# STM32.net
KiCad netlist of a schematic drawn in Altium Designer
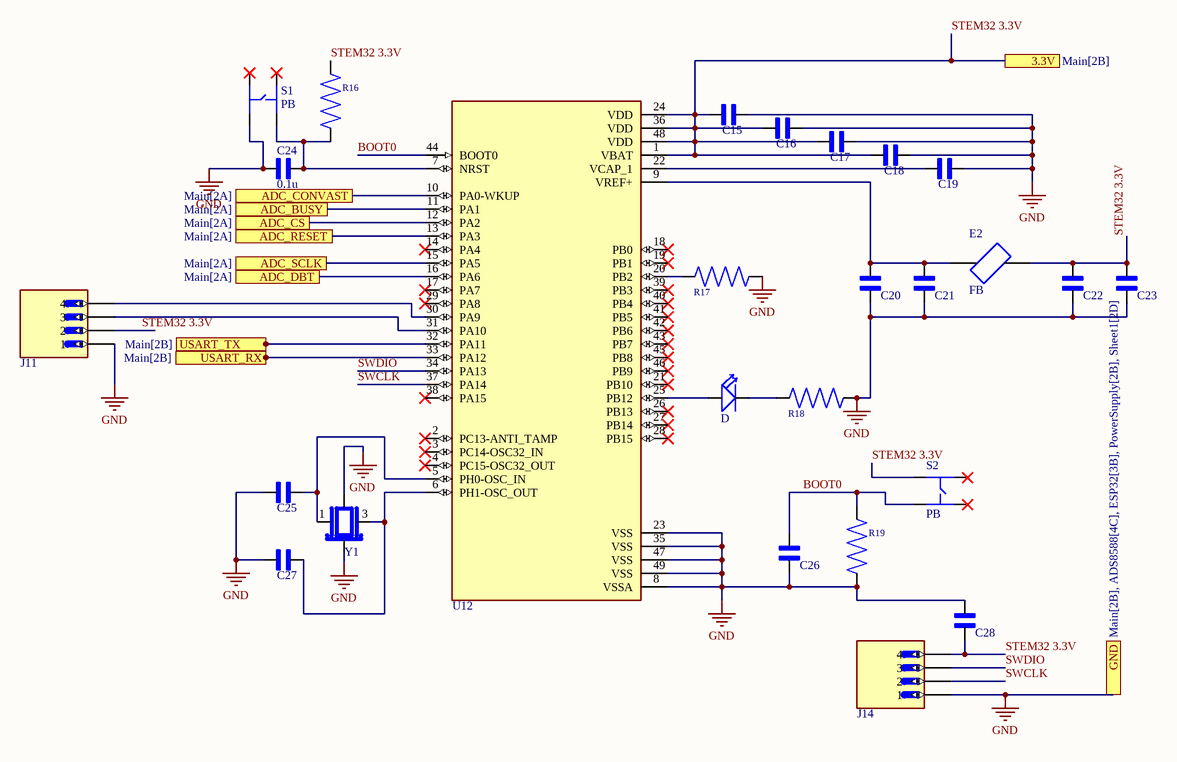
[diagram p0: STM32.SchDoc]

(export (version "E")
  (design (tool "Eeschema 10.0.6"))
  (components
    (comp (ref "C15")
      (value "CAP603")
      (footprint "CAP603")
      (description "0.1 ÂµF Â±5% 10V Ceramic Capacitor X7R 0603 (1608 Metric)")
      (fields (field (name "MF") "Vishay") (field (name "MP") "VJ0603Y104JXQCW1BC"))
      (libsource (lib "ESP32-S3-WROOM-1-N16R8") (part "CAP603"))
    )
    (comp (ref "C16")
      (value "CAP603")
      (footprint "CAP603")
      (description "0.1 ÂµF Â±5% 10V Ceramic Capacitor X7R 0603 (1608 Metric)")
      (fields (field (name "MF") "Vishay") (field (name "MP") "VJ0603Y104JXQCW1BC"))
      (libsource (lib "ESP32-S3-WROOM-1-N16R8") (part "CAP603"))
    )
    (comp (ref "C17")
      (value "CAP603")
      (footprint "CAP603")
      (description "0.1 ÂµF Â±5% 10V Ceramic Capacitor X7R 0603 (1608 Metric)")
      (fields (field (name "MF") "Vishay") (field (name "MP") "VJ0603Y104JXQCW1BC"))
      (libsource (lib "ESP32-S3-WROOM-1-N16R8") (part "CAP603"))
    )
    (comp (ref "C18")
      (value "CAP603")
      (footprint "CAP603")
      (description "0.1 ÂµF Â±5% 10V Ceramic Capacitor X7R 0603 (1608 Metric)")
      (fields (field (name "MF") "Vishay") (field (name "MP") "VJ0603Y104JXQCW1BC"))
      (libsource (lib "ESP32-S3-WROOM-1-N16R8") (part "CAP603"))
    )
    (comp (ref "C19")
      (value "CAP603")
      (footprint "CAP603")
      (description "0.1 ÂµF Â±5% 10V Ceramic Capacitor X7R 0603 (1608 Metric)")
      (fields (field (name "MF") "Vishay") (field (name "MP") "VJ0603Y104JXQCW1BC"))
      (libsource (lib "ESP32-S3-WROOM-1-N16R8") (part "CAP603"))
    )
    (comp (ref "C20")
      (value "CAP603")
      (footprint "CAP603")
      (description "0.1 ÂµF Â±5% 10V Ceramic Capacitor X7R 0603 (1608 Metric)")
      (fields (field (name "MF") "Vishay") (field (name "MP") "VJ0603Y104JXQCW1BC"))
      (libsource (lib "") (part "CAP603_1"))
    )
    (comp (ref "C21")
      (value "CAP603")
      (footprint "CAP603")
      (description "0.1 ÂµF Â±5% 10V Ceramic Capacitor X7R 0603 (1608 Metric)")
      (fields (field (name "MF") "Vishay") (field (name "MP") "VJ0603Y104JXQCW1BC"))
      (libsource (lib "") (part "CAP603_1"))
    )
    (comp (ref "C22")
      (value "CAP603")
      (footprint "CAP603")
      (description "0.1 ÂµF Â±5% 10V Ceramic Capacitor X7R 0603 (1608 Metric)")
      (fields (field (name "MF") "Vishay") (field (name "MP") "VJ0603Y104JXQCW1BC"))
      (libsource (lib "") (part "CAP603_1"))
    )
    (comp (ref "C23")
      (value "CAP603")
      (footprint "CAP603")
      (description "0.1 ÂµF Â±5% 10V Ceramic Capacitor X7R 0603 (1608 Metric)")
      (fields (field (name "MF") "Vishay") (field (name "MP") "VJ0603Y104JXQCW1BC"))
      (libsource (lib "") (part "CAP603_1"))
    )
    (comp (ref "C24")
      (value "0.1u")
      (footprint "0603Capacitor")
      (description "100nf,X7R,50V")
      (fields (field (name "MF") "AVX") (field (name "MP") "0603YC223KAT2A"))
      (libsource (lib "Schlib1") (part "0603_0.1u"))
    )
    (comp (ref "C25")
      (value "CAP603")
      (footprint "CAP603")
      (description "0.1 ÂµF Â±5% 10V Ceramic Capacitor X7R 0603 (1608 Metric)")
      (fields (field (name "MF") "Vishay") (field (name "MP") "VJ0603Y104JXQCW1BC"))
      (libsource (lib "ESP32-S3-WROOM-1-N16R8") (part "CAP603"))
    )
    (comp (ref "C26")
      (value "CAP603")
      (footprint "CAP603")
      (description "0.1 ÂµF Â±5% 10V Ceramic Capacitor X7R 0603 (1608 Metric)")
      (fields (field (name "MF") "Vishay") (field (name "MP") "VJ0603Y104JXQCW1BC"))
      (libsource (lib "") (part "CAP603_1"))
    )
    (comp (ref "C27")
      (value "CAP603")
      (footprint "CAP603")
      (description "0.1 ÂµF Â±5% 10V Ceramic Capacitor X7R 0603 (1608 Metric)")
      (fields (field (name "MF") "Vishay") (field (name "MP") "VJ0603Y104JXQCW1BC"))
      (libsource (lib "ESP32-S3-WROOM-1-N16R8") (part "CAP603"))
    )
    (comp (ref "C28")
      (value "CAP603")
      (footprint "CAP603")
      (description "0.1 ÂµF Â±5% 10V Ceramic Capacitor X7R 0603 (1608 Metric)")
      (fields (field (name "MF") "Vishay") (field (name "MP") "VJ0603Y104JXQCW1BC"))
      (libsource (lib "") (part "CAP603_1"))
    )
    (comp (ref "D")
      (value "SMD-LED-YELLOW-WHITE(0603)")
      (footprint "LED-0603")
      (description "SMD LED Yellow-White")
      (fields (field (name "MF") "Chengguangxing") (field (name "MP") "ADL-0603W"))
      (libsource (lib "ESP32-S3-WROOM-1-N16R8") (part "SMD-LED-YELLOW-WHITE(0603)"))
    )
    (comp (ref "E2")
      (value "FB")
      (footprint "FB_MI1206K601R-10")
      (description "600 Ohms @ 100 MHz 1 Power, Signal Line Ferrite Bead 1206 (3216 Metric) 1.5A 80mOhm")
      (fields (field (name "MF") "Laird-Signal Integrity") (field (name "MP") "MI1206K601R-10"))
      (libsource (lib "Schlib1") (part "MI1206K601R-10"))
    )
    (comp (ref "J11")
      (value "4-pin header")
      (footprint "4-pin header")
      (fields (field (name "MF") "FCI") (field (name "MP") "68000-104HLF"))
      (libsource (lib "ESP32-S3-WROOM-1-N16R8") (part "4-pin header"))
    )
    (comp (ref "J14")
      (value "4-pin header")
      (footprint "4-pin header")
      (fields (field (name "MF") "FCI") (field (name "MP") "68000-104HLF"))
      (libsource (lib "ESP32-S3-WROOM-1-N16R8") (part "4-pin header"))
    )
    (comp (ref "R16")
      (value "RES-603")
      (footprint "CAP603")
      (fields (field (name "MF") "Yageo") (field (name "MP") "RC0805FR-0710KL"))
      (libsource (lib "ESP32-S3-WROOM-1-N16R8") (part "RES-603"))
    )
    (comp (ref "R17")
      (value "RES-603")
      (footprint "CAP603")
      (fields (field (name "MF") "Yageo") (field (name "MP") "RC0805FR-0710KL"))
      (libsource (lib "ESP32-S3-WROOM-1-N16R8") (part "RES-603"))
    )
    (comp (ref "R18")
      (value "RES-603")
      (footprint "CAP603")
      (fields (field (name "MF") "Yageo") (field (name "MP") "RC0805FR-0710KL"))
      (libsource (lib "ESP32-S3-WROOM-1-N16R8") (part "RES-603"))
    )
    (comp (ref "R19")
      (value "RES-603")
      (footprint "CAP603")
      (fields (field (name "MF") "Yageo") (field (name "MP") "RC0805FR-0710KL"))
      (libsource (lib "ESP32-S3-WROOM-1-N16R8") (part "RES-603"))
    )
    (comp (ref "S1") (value "PB") (footprint "Push_button") (libsource (lib "Schlib1") (part "PushButton")))
    (comp (ref "S2") (value "PB") (footprint "Push_button") (libsource (lib "Schlib1") (part "PushButton")))
    (comp (ref "U12")
      (value "STM32F411CEU6TR")
      (footprint "STM32F411CEU6TR")
      (fields (field (name "MF") "STMicroelectronics"))
      (libsource (lib "ESP32-S3-WROOM-1-N16R8") (part "STM32F411CEU6TR"))
    )
    (comp (ref "Y1")
      (value "25 MHz oscillator")
      (footprint "25 MHz oscillator")
      (description "25 MHz 10ppm Crystal 18pF 30 Ohms 4-SMD, No Lead (3.20mm x 2.50mm)")
      (fields (field (name "MF") "Raltron Electronics") (field (name "MP") "RH100-25.000-18-F-1015-TR-NS2"))
      (libsource (lib "ESP32-S3-WROOM-1-N16R8") (part "25 MHz oscillator"))
    )
  )
  (nets
    (net (code "1") (name "/ADC_BUSY") (class "Default")
      (node (ref "U12") (pin "11") (pinfunction "PA1_11") (pintype "bidirectional"))
    )
    (net (code "2") (name "/ADC_CONVAST") (class "Default")
      (node (ref "U12") (pin "10") (pinfunction "PA0-WKUP_10") (pintype "bidirectional"))
    )
    (net (code "3") (name "/ADC_CS") (class "Default")
      (node (ref "U12") (pin "12") (pinfunction "PA2_12") (pintype "bidirectional"))
    )
    (net (code "4") (name "/ADC_DBT") (class "Default")
      (node (ref "U12") (pin "16") (pinfunction "PA6_16") (pintype "bidirectional"))
    )
    (net (code "5") (name "/ADC_RESET") (class "Default")
      (node (ref "U12") (pin "13") (pinfunction "PA3_13") (pintype "bidirectional"))
    )
    (net (code "6") (name "/ADC_SCLK") (class "Default")
      (node (ref "U12") (pin "15") (pinfunction "PA5_15") (pintype "bidirectional"))
    )
    (net (code "7") (name "/BOOT0") (class "Default")
      (node (ref "C26") (pin "2") (pinfunction "2_2") (pintype "passive"))
      (node (ref "R19") (pin "2") (pinfunction "2_2") (pintype "passive"))
      (node (ref "S2") (pin "3") (pinfunction "3_3") (pintype "passive"))
      (node (ref "U12") (pin "44") (pinfunction "BOOT0_44") (pintype "input"))
    )
    (net (code "8") (name "/STEM32 3.3V") (class "Default")
      (node (ref "C15") (pin "1") (pinfunction "1_1") (pintype "passive"))
      (node (ref "C16") (pin "1") (pinfunction "1_1") (pintype "passive"))
      (node (ref "C17") (pin "1") (pinfunction "1_1") (pintype "passive"))
      (node (ref "C18") (pin "1") (pinfunction "1_1") (pintype "passive"))
      (node (ref "C22") (pin "2") (pinfunction "2_2") (pintype "passive"))
      (node (ref "C23") (pin "2") (pinfunction "2_2") (pintype "passive"))
      (node (ref "C28") (pin "1") (pinfunction "1_1") (pintype "passive"))
      (node (ref "E2") (pin "2") (pinfunction "2_2") (pintype "passive"))
      (node (ref "J11") (pin "2") (pinfunction "2_2") (pintype "bidirectional"))
      (node (ref "J14") (pin "4") (pinfunction "4_4") (pintype "bidirectional"))
      (node (ref "R16") (pin "2") (pinfunction "2_2") (pintype "passive"))
      (node (ref "S2") (pin "1") (pinfunction "1_1") (pintype "passive"))
      (node (ref "U12") (pin "1") (pinfunction "VBAT_1") (pintype "passive"))
      (node (ref "U12") (pin "24") (pinfunction "VDD_24") (pintype "passive"))
      (node (ref "U12") (pin "36") (pinfunction "VDD_36") (pintype "passive"))
      (node (ref "U12") (pin "48") (pinfunction "VDD_48") (pintype "passive"))
    )
    (net (code "9") (name "/SWCLK") (class "Default")
      (node (ref "J14") (pin "2") (pinfunction "2_2") (pintype "bidirectional"))
      (node (ref "U12") (pin "37") (pinfunction "PA14_37") (pintype "bidirectional"))
    )
    (net (code "10") (name "/SWDIO") (class "Default")
      (node (ref "J14") (pin "3") (pinfunction "3_3") (pintype "bidirectional"))
      (node (ref "U12") (pin "34") (pinfunction "PA13_34") (pintype "bidirectional"))
    )
    (net (code "11") (name "/USART_RX") (class "Default")
      (node (ref "U12") (pin "33") (pinfunction "PA12_33") (pintype "bidirectional"))
    )
    (net (code "12") (name "/USART_TX") (class "Default")
      (node (ref "U12") (pin "32") (pinfunction "PA11_32") (pintype "bidirectional"))
    )
    (net (code "13") (name "GND") (class "Default")
      (node (ref "C15") (pin "2") (pinfunction "2_2") (pintype "passive"))
      (node (ref "C16") (pin "2") (pinfunction "2_2") (pintype "passive"))
      (node (ref "C17") (pin "2") (pinfunction "2_2") (pintype "passive"))
      (node (ref "C18") (pin "2") (pinfunction "2_2") (pintype "passive"))
      (node (ref "C19") (pin "2") (pinfunction "2_2") (pintype "passive"))
      (node (ref "C20") (pin "1") (pinfunction "1_1") (pintype "passive"))
      (node (ref "C21") (pin "1") (pinfunction "1_1") (pintype "passive"))
      (node (ref "C22") (pin "1") (pinfunction "1_1") (pintype "passive"))
      (node (ref "C23") (pin "1") (pinfunction "1_1") (pintype "passive"))
      (node (ref "C24") (pin "1") (pinfunction "1_1") (pintype "passive"))
      (node (ref "C25") (pin "1") (pinfunction "1_1") (pintype "passive"))
      (node (ref "C26") (pin "1") (pinfunction "1_1") (pintype "passive"))
      (node (ref "C27") (pin "1") (pinfunction "1_1") (pintype "passive"))
      (node (ref "C28") (pin "2") (pinfunction "2_2") (pintype "passive"))
      (node (ref "J11") (pin "1") (pinfunction "1_1") (pintype "bidirectional"))
      (node (ref "J14") (pin "1") (pinfunction "1_1") (pintype "bidirectional"))
      (node (ref "R17") (pin "2") (pinfunction "2_2") (pintype "passive"))
      (node (ref "R18") (pin "2") (pinfunction "2_2") (pintype "passive"))
      (node (ref "R19") (pin "1") (pinfunction "1_1") (pintype "passive"))
      (node (ref "S1") (pin "1") (pinfunction "1_1") (pintype "passive"))
      (node (ref "U12") (pin "23") (pinfunction "VSS_23") (pintype "passive"))
      (node (ref "U12") (pin "35") (pinfunction "VSS_35") (pintype "passive"))
      (node (ref "U12") (pin "47") (pinfunction "VSS_47") (pintype "passive"))
      (node (ref "U12") (pin "49") (pinfunction "VSS_49") (pintype "passive"))
      (node (ref "U12") (pin "8") (pinfunction "VSSA_8") (pintype "passive"))
      (node (ref "Y1") (pin "2") (pinfunction "GND_2") (pintype "power_in"))
      (node (ref "Y1") (pin "4") (pinfunction "GND_4") (pintype "power_in"))
    )
    (net (code "14") (name "Net-(D-PadNEG)") (class "Default")
      (node (ref "D") (pin "NEG") (pinfunction "NEG_NEG") (pintype "passive"))
      (node (ref "R18") (pin "1") (pinfunction "1_1") (pintype "passive"))
    )
    (net (code "15") (name "Net-(U12-NRST)") (class "Default")
      (node (ref "C24") (pin "2") (pinfunction "2_2") (pintype "passive"))
      (node (ref "R16") (pin "1") (pinfunction "1_1") (pintype "passive"))
      (node (ref "S1") (pin "3") (pinfunction "3_3") (pintype "passive"))
      (node (ref "U12") (pin "7") (pinfunction "NRST_7") (pintype "bidirectional"))
    )
    (net (code "16") (name "Net-(U12-PA9)") (class "Default")
      (node (ref "J11") (pin "4") (pinfunction "4_4") (pintype "bidirectional"))
      (node (ref "U12") (pin "30") (pinfunction "PA9_30") (pintype "bidirectional"))
    )
    (net (code "17") (name "Net-(U12-PA10)") (class "Default")
      (node (ref "J11") (pin "3") (pinfunction "3_3") (pintype "bidirectional"))
      (node (ref "U12") (pin "31") (pinfunction "PA10_31") (pintype "bidirectional"))
    )
    (net (code "18") (name "Net-(U12-PB2)") (class "Default")
      (node (ref "R17") (pin "1") (pinfunction "1_1") (pintype "passive"))
      (node (ref "U12") (pin "20") (pinfunction "PB2_20") (pintype "bidirectional"))
    )
    (net (code "19") (name "Net-(U12-PB12)") (class "Default")
      (node (ref "D") (pin "POS") (pinfunction "POS_POS") (pintype "passive"))
      (node (ref "U12") (pin "25") (pinfunction "PB12_25") (pintype "bidirectional"))
    )
    (net (code "20") (name "Net-(U12-PH0-OSC_IN)") (class "Default")
      (node (ref "C25") (pin "2") (pinfunction "2_2") (pintype "passive"))
      (node (ref "U12") (pin "5") (pinfunction "PH0-OSC_IN_5") (pintype "bidirectional"))
      (node (ref "Y1") (pin "1") (pinfunction "1_1") (pintype "passive"))
    )
    (net (code "21") (name "Net-(U12-PH1-OSC_OUT)") (class "Default")
      (node (ref "C27") (pin "2") (pinfunction "2_2") (pintype "passive"))
      (node (ref "U12") (pin "6") (pinfunction "PH1-OSC_OUT_6") (pintype "bidirectional"))
      (node (ref "Y1") (pin "3") (pinfunction "3_3") (pintype "passive"))
    )
    (net (code "22") (name "Net-(U12-VCAP_1)") (class "Default")
      (node (ref "C19") (pin "1") (pinfunction "1_1") (pintype "passive"))
      (node (ref "U12") (pin "22") (pinfunction "VCAP_1_22") (pintype "power_in"))
    )
    (net (code "23") (name "Net-(U12-VREF+)") (class "Default")
      (node (ref "C20") (pin "2") (pinfunction "2_2") (pintype "passive"))
      (node (ref "C21") (pin "2") (pinfunction "2_2") (pintype "passive"))
      (node (ref "E2") (pin "1") (pinfunction "1_1") (pintype "passive"))
      (node (ref "U12") (pin "9") (pinfunction "VREF+_9") (pintype "power_in"))
    )
    (net (code "24") (name "unconnected-(S1-Pad2)") (class "Default")
      (node (ref "S1") (pin "2") (pinfunction "2_2") (pintype "passive+no_connect"))
    )
    (net (code "25") (name "unconnected-(S1-Pad4)") (class "Default")
      (node (ref "S1") (pin "4") (pinfunction "4_4") (pintype "passive"))
    )
    (net (code "26") (name "unconnected-(S2-Pad2)") (class "Default")
      (node (ref "S2") (pin "2") (pinfunction "2_2") (pintype "passive+no_connect"))
    )
    (net (code "27") (name "unconnected-(S2-Pad4)") (class "Default")
      (node (ref "S2") (pin "4") (pinfunction "4_4") (pintype "passive"))
    )
    (net (code "28") (name "unconnected-(U12-PA4-Pad14)") (class "Default")
      (node (ref "U12") (pin "14") (pinfunction "PA4_14") (pintype "bidirectional+no_connect"))
    )
    (net (code "29") (name "unconnected-(U12-PA7-Pad17)") (class "Default")
      (node (ref "U12") (pin "17") (pinfunction "PA7_17") (pintype "bidirectional+no_connect"))
    )
    (net (code "30") (name "unconnected-(U12-PA8-Pad29)") (class "Default")
      (node (ref "U12") (pin "29") (pinfunction "PA8_29") (pintype "bidirectional+no_connect"))
    )
    (net (code "31") (name "unconnected-(U12-PA15-Pad38)") (class "Default")
      (node (ref "U12") (pin "38") (pinfunction "PA15_38") (pintype "bidirectional+no_connect"))
    )
    (net (code "32") (name "unconnected-(U12-PB0-Pad18)") (class "Default")
      (node (ref "U12") (pin "18") (pinfunction "PB0_18") (pintype "bidirectional+no_connect"))
    )
    (net (code "33") (name "unconnected-(U12-PB1-Pad19)") (class "Default")
      (node (ref "U12") (pin "19") (pinfunction "PB1_19") (pintype "bidirectional+no_connect"))
    )
    (net (code "34") (name "unconnected-(U12-PB3-Pad39)") (class "Default")
      (node (ref "U12") (pin "39") (pinfunction "PB3_39") (pintype "bidirectional+no_connect"))
    )
    (net (code "35") (name "unconnected-(U12-PB4-Pad40)") (class "Default")
      (node (ref "U12") (pin "40") (pinfunction "PB4_40") (pintype "bidirectional+no_connect"))
    )
    (net (code "36") (name "unconnected-(U12-PB5-Pad41)") (class "Default")
      (node (ref "U12") (pin "41") (pinfunction "PB5_41") (pintype "bidirectional+no_connect"))
    )
    (net (code "37") (name "unconnected-(U12-PB6-Pad42)") (class "Default")
      (node (ref "U12") (pin "42") (pinfunction "PB6_42") (pintype "bidirectional+no_connect"))
    )
    (net (code "38") (name "unconnected-(U12-PB7-Pad43)") (class "Default")
      (node (ref "U12") (pin "43") (pinfunction "PB7_43") (pintype "bidirectional+no_connect"))
    )
    (net (code "39") (name "unconnected-(U12-PB8-Pad45)") (class "Default")
      (node (ref "U12") (pin "45") (pinfunction "PB8_45") (pintype "bidirectional+no_connect"))
    )
    (net (code "40") (name "unconnected-(U12-PB9-Pad46)") (class "Default")
      (node (ref "U12") (pin "46") (pinfunction "PB9_46") (pintype "bidirectional+no_connect"))
    )
    (net (code "41") (name "unconnected-(U12-PB10-Pad21)") (class "Default")
      (node (ref "U12") (pin "21") (pinfunction "PB10_21") (pintype "bidirectional+no_connect"))
    )
    (net (code "42") (name "unconnected-(U12-PB13-Pad26)") (class "Default")
      (node (ref "U12") (pin "26") (pinfunction "PB13_26") (pintype "bidirectional+no_connect"))
    )
    (net (code "43") (name "unconnected-(U12-PB14-Pad27)") (class "Default")
      (node (ref "U12") (pin "27") (pinfunction "PB14_27") (pintype "bidirectional+no_connect"))
    )
    (net (code "44") (name "unconnected-(U12-PB15-Pad28)") (class "Default")
      (node (ref "U12") (pin "28") (pinfunction "PB15_28") (pintype "bidirectional+no_connect"))
    )
    (net (code "45") (name "unconnected-(U12-PC13-ANTI_TAMP-Pad2)") (class "Default")
      (node (ref "U12") (pin "2") (pinfunction "PC13-ANTI_TAMP_2") (pintype "bidirectional+no_connect"))
    )
    (net (code "46") (name "unconnected-(U12-PC14-OSC32_IN-Pad3)") (class "Default")
      (node (ref "U12") (pin "3") (pinfunction "PC14-OSC32_IN_3") (pintype "bidirectional+no_connect"))
    )
    (net (code "47") (name "unconnected-(U12-PC15-OSC32_OUT-Pad4)") (class "Default")
      (node (ref "U12") (pin "4") (pinfunction "PC15-OSC32_OUT_4") (pintype "bidirectional+no_connect"))
    )
  )
)
